# esp32_relay_attempt_1.net
KiCad netlist of a schematic drawn in EAGLE
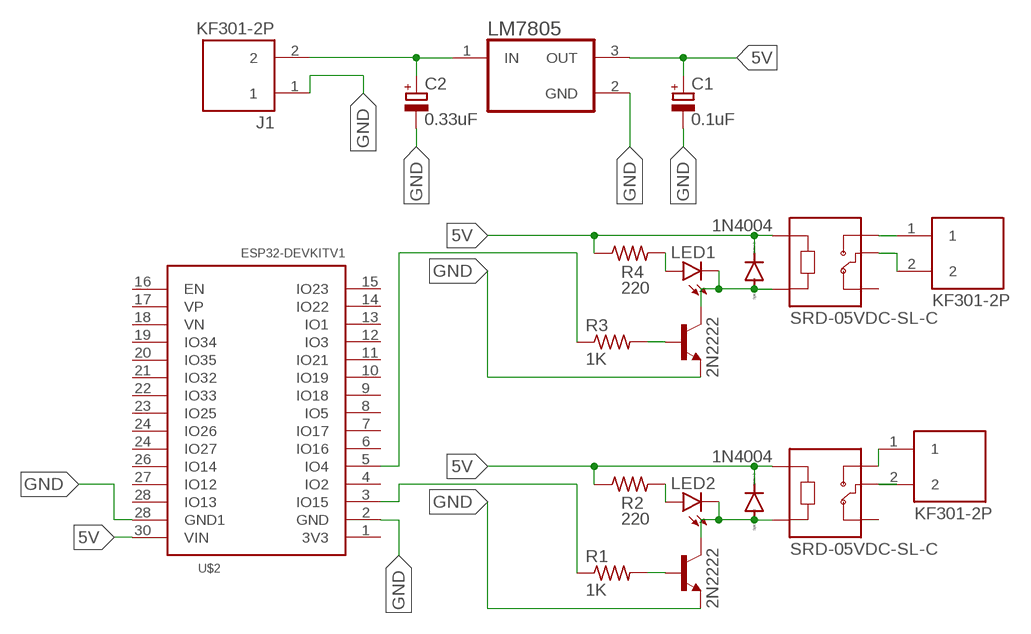
[diagram p0: schematic, sheet 1]

(export (version "E")
  (design (tool "Eeschema 10.0.6"))
  (components
    (comp (ref "C1")
      (value "0.1uF")
      (footprint "eagle-import:E2,5-6")
      (libsource (lib "eagle-import") (part "CPOL-EUE2.5-6"))
    )
    (comp (ref "C2")
      (value "0.33uF")
      (footprint "eagle-import:E2,5-6")
      (libsource (lib "eagle-import") (part "CPOL-EUE2.5-6"))
    )
    (comp (ref "D1")
      (value "1N4004")
      (footprint "eagle-import:DO41-10")
      (libsource (lib "eagle-import") (part "1N4004"))
    )
    (comp (ref "D2")
      (value "1N4004")
      (footprint "eagle-import:DO41-10")
      (libsource (lib "eagle-import") (part "1N4004"))
    )
    (comp (ref "J1")
      (value "KF301-2P")
      (footprint "eagle-import:HANDSON_KF301-2P")
      (fields (field (name "MF") "Handson Technology"))
      (libsource (lib "eagle-import") (part "KF301-2P"))
    )
    (comp (ref "J2")
      (value "KF301-2P")
      (footprint "eagle-import:HANDSON_KF301-2P")
      (fields (field (name "MF") "Handson Technology"))
      (libsource (lib "eagle-import") (part "KF301-2P"))
    )
    (comp (ref "J3")
      (value "KF301-2P")
      (footprint "eagle-import:HANDSON_KF301-2P")
      (fields (field (name "MF") "Handson Technology"))
      (libsource (lib "eagle-import") (part "KF301-2P"))
    )
    (comp (ref "K1")
      (value "SRD-05VDC-SL-C")
      (footprint "eagle-import:RELAY_SRD-05VDC-SL-C")
      (fields (field (name "MF") "Songle Relay"))
      (libsource (lib "eagle-import") (part "SRD-05VDC-SL-C"))
    )
    (comp (ref "K2")
      (value "SRD-05VDC-SL-C")
      (footprint "eagle-import:RELAY_SRD-05VDC-SL-C")
      (fields (field (name "MF") "Songle Relay"))
      (libsource (lib "eagle-import") (part "SRD-05VDC-SL-C"))
    )
    (comp (ref "LED1")
      (value "LED5MM")
      (footprint "eagle-import:LED5MM")
      (libsource (lib "eagle-import") (part "LED5MM"))
    )
    (comp (ref "LED2")
      (value "LED5MM")
      (footprint "eagle-import:LED5MM")
      (libsource (lib "eagle-import") (part "LED5MM"))
    )
    (comp (ref "LM7805")
      (value "LM7805CT/NOPB")
      (footprint "eagle-import:TO254P1054X470X2600-3")
      (fields (field (name "MF") "ON Semiconductor") (field (name "MP") "LM7805CT"))
      (libsource (lib "eagle-import") (part "LM7805CT/NOPB"))
    )
    (comp (ref "R1")
      (value "1K")
      (footprint "eagle-import:0204_7")
      (libsource (lib "eagle-import") (part "R-US_0204/7"))
    )
    (comp (ref "R2")
      (value "220")
      (footprint "eagle-import:0204_7")
      (libsource (lib "eagle-import") (part "R-US_0204/7"))
    )
    (comp (ref "R3")
      (value "1K")
      (footprint "eagle-import:0204_7")
      (libsource (lib "eagle-import") (part "R-US_0204/7"))
    )
    (comp (ref "R4")
      (value "220")
      (footprint "eagle-import:0204_7")
      (libsource (lib "eagle-import") (part "R-US_0204/7"))
    )
    (comp (ref "T1")
      (value "2N2222")
      (footprint "eagle-import:TO92-EBC-OVAL")
      (libsource (lib "eagle-import") (part "2N2222"))
    )
    (comp (ref "T2")
      (value "2N2222")
      (footprint "eagle-import:TO92-EBC-OVAL")
      (libsource (lib "eagle-import") (part "2N2222"))
    )
    (comp (ref "U$2")
      (value "ESP32DEVKITV1")
      (footprint "eagle-import:ESP32-DEVKITV1")
      (libsource (lib "eagle-import") (part "ESP32DEVKITV1"))
    )
  )
  (nets
    (net (code "1") (name "5V") (class "Default")
      (node (ref "C1") (pin "+") (pinfunction "+_+") (pintype "passive"))
      (node (ref "D1") (pin "C") (pinfunction "C_C") (pintype "passive"))
      (node (ref "D2") (pin "C") (pinfunction "C_C") (pintype "passive"))
      (node (ref "K1") (pin "A1") (pinfunction "A1_A1") (pintype "passive"))
      (node (ref "K2") (pin "A1") (pinfunction "A1_A1") (pintype "passive"))
      (node (ref "LM7805") (pin "3") (pinfunction "OUT_3") (pintype "output"))
      (node (ref "R2") (pin "1") (pinfunction "1_1") (pintype "passive"))
      (node (ref "R4") (pin "1") (pinfunction "1_1") (pintype "passive"))
      (node (ref "U$2") (pin "30") (pinfunction "VIN_30") (pintype "bidirectional"))
    )
    (net (code "2") (name "GND") (class "Default")
      (node (ref "C1") (pin "-") (pinfunction "-_-") (pintype "passive"))
      (node (ref "C2") (pin "-") (pinfunction "-_-") (pintype "passive"))
      (node (ref "J1") (pin "1") (pinfunction "1_1") (pintype "passive"))
      (node (ref "LM7805") (pin "2") (pinfunction "GND_2") (pintype "power_in"))
      (node (ref "T1") (pin "E") (pinfunction "E_E") (pintype "passive"))
      (node (ref "T2") (pin "E") (pinfunction "E_E") (pintype "passive"))
      (node (ref "U$2") (pin "2") (pinfunction "GND_2") (pintype "bidirectional"))
      (node (ref "U$2") (pin "28") (pinfunction "GND1_28") (pintype "bidirectional"))
    )
    (net (code "3") (name "Net-(J2-Pad1)") (class "Default")
      (node (ref "J2") (pin "1") (pinfunction "1_1") (pintype "passive"))
      (node (ref "K1") (pin "NO") (pinfunction "NO_NO") (pintype "passive"))
    )
    (net (code "4") (name "Net-(J2-Pad2)") (class "Default")
      (node (ref "J2") (pin "2") (pinfunction "2_2") (pintype "passive"))
      (node (ref "K1") (pin "COM") (pinfunction "COM_COM") (pintype "passive"))
    )
    (net (code "5") (name "Net-(J3-Pad1)") (class "Default")
      (node (ref "J3") (pin "1") (pinfunction "1_1") (pintype "passive"))
      (node (ref "K2") (pin "NO") (pinfunction "NO_NO") (pintype "passive"))
    )
    (net (code "6") (name "Net-(J3-Pad2)") (class "Default")
      (node (ref "J3") (pin "2") (pinfunction "2_2") (pintype "passive"))
      (node (ref "K2") (pin "COM") (pinfunction "COM_COM") (pintype "passive"))
    )
    (net (code "7") (name "Net-(LED1-C)") (class "Default")
      (node (ref "D1") (pin "A") (pinfunction "A_A") (pintype "passive"))
      (node (ref "K1") (pin "A2") (pinfunction "A2_A2") (pintype "passive"))
      (node (ref "LED1") (pin "K") (pinfunction "C_K") (pintype "passive"))
      (node (ref "T1") (pin "C") (pinfunction "C_C") (pintype "passive"))
    )
    (net (code "8") (name "Net-(LED1-PadA)") (class "Default")
      (node (ref "LED1") (pin "A") (pinfunction "A_A") (pintype "passive"))
      (node (ref "R4") (pin "2") (pinfunction "2_2") (pintype "passive"))
    )
    (net (code "9") (name "Net-(LED2-C)") (class "Default")
      (node (ref "D2") (pin "A") (pinfunction "A_A") (pintype "passive"))
      (node (ref "K2") (pin "A2") (pinfunction "A2_A2") (pintype "passive"))
      (node (ref "LED2") (pin "K") (pinfunction "C_K") (pintype "passive"))
      (node (ref "T2") (pin "C") (pinfunction "C_C") (pintype "passive"))
    )
    (net (code "10") (name "Net-(LED2-PadA)") (class "Default")
      (node (ref "LED2") (pin "A") (pinfunction "A_A") (pintype "passive"))
      (node (ref "R2") (pin "2") (pinfunction "2_2") (pintype "passive"))
    )
    (net (code "11") (name "Net-(LM7805-IN)") (class "Default")
      (node (ref "C2") (pin "+") (pinfunction "+_+") (pintype "passive"))
      (node (ref "J1") (pin "2") (pinfunction "2_2") (pintype "passive"))
      (node (ref "LM7805") (pin "1") (pinfunction "IN_1") (pintype "input"))
    )
    (net (code "12") (name "Net-(R1-Pad2)") (class "Default")
      (node (ref "R1") (pin "2") (pinfunction "2_2") (pintype "passive"))
      (node (ref "T2") (pin "B") (pinfunction "B_B") (pintype "passive"))
    )
    (net (code "13") (name "Net-(R3-Pad2)") (class "Default")
      (node (ref "R3") (pin "2") (pinfunction "2_2") (pintype "passive"))
      (node (ref "T1") (pin "B") (pinfunction "B_B") (pintype "passive"))
    )
    (net (code "14") (name "Net-(U$2-IO4)") (class "Default")
      (node (ref "R3") (pin "1") (pinfunction "1_1") (pintype "passive"))
      (node (ref "U$2") (pin "5") (pinfunction "IO4_5") (pintype "bidirectional"))
    )
    (net (code "15") (name "Net-(U$2-IO15)") (class "Default")
      (node (ref "R1") (pin "1") (pinfunction "1_1") (pintype "passive"))
      (node (ref "U$2") (pin "3") (pinfunction "IO15_3") (pintype "bidirectional"))
    )
    (net (code "16") (name "unconnected-(K1-PadNC)") (class "Default")
      (node (ref "K1") (pin "NC") (pinfunction "NC_NC") (pintype "passive"))
    )
    (net (code "17") (name "unconnected-(K2-PadNC)") (class "Default")
      (node (ref "K2") (pin "NC") (pinfunction "NC_NC") (pintype "passive"))
    )
    (net (code "18") (name "unconnected-(U$2-3V3-Pad1)") (class "Default")
      (node (ref "U$2") (pin "1") (pinfunction "3V3_1") (pintype "bidirectional"))
    )
    (net (code "19") (name "unconnected-(U$2-EN-Pad16)") (class "Default")
      (node (ref "U$2") (pin "16") (pinfunction "EN_16") (pintype "bidirectional"))
    )
    (net (code "20") (name "unconnected-(U$2-IO1-Pad13)") (class "Default")
      (node (ref "U$2") (pin "13") (pinfunction "IO1_13") (pintype "bidirectional"))
    )
    (net (code "21") (name "unconnected-(U$2-IO2-Pad4)") (class "Default")
      (node (ref "U$2") (pin "4") (pinfunction "IO2_4") (pintype "bidirectional"))
    )
    (net (code "22") (name "unconnected-(U$2-IO3-Pad12)") (class "Default")
      (node (ref "U$2") (pin "12") (pinfunction "IO3_12") (pintype "bidirectional"))
    )
    (net (code "23") (name "unconnected-(U$2-IO5-Pad8)") (class "Default")
      (node (ref "U$2") (pin "8") (pinfunction "IO5_8") (pintype "bidirectional"))
    )
    (net (code "24") (name "unconnected-(U$2-IO12-Pad27)") (class "Default")
      (node (ref "U$2") (pin "27") (pinfunction "IO12_27") (pintype "bidirectional"))
    )
    (net (code "25") (name "unconnected-(U$2-IO13-Pad28)") (class "Default")
      (node (ref "U$2") (pin "28") (pinfunction "IO13_28") (pintype "bidirectional"))
    )
    (net (code "26") (name "unconnected-(U$2-IO14-Pad26)") (class "Default")
      (node (ref "U$2") (pin "26") (pinfunction "IO14_26") (pintype "bidirectional"))
    )
    (net (code "27") (name "unconnected-(U$2-IO16-Pad6)") (class "Default")
      (node (ref "U$2") (pin "6") (pinfunction "IO16_6") (pintype "bidirectional"))
    )
    (net (code "28") (name "unconnected-(U$2-IO17-Pad7)") (class "Default")
      (node (ref "U$2") (pin "7") (pinfunction "IO17_7") (pintype "bidirectional"))
    )
    (net (code "29") (name "unconnected-(U$2-IO18-Pad9)") (class "Default")
      (node (ref "U$2") (pin "9") (pinfunction "IO18_9") (pintype "bidirectional"))
    )
    (net (code "30") (name "unconnected-(U$2-IO19-Pad10)") (class "Default")
      (node (ref "U$2") (pin "10") (pinfunction "IO19_10") (pintype "bidirectional"))
    )
    (net (code "31") (name "unconnected-(U$2-IO21-Pad11)") (class "Default")
      (node (ref "U$2") (pin "11") (pinfunction "IO21_11") (pintype "bidirectional"))
    )
    (net (code "32") (name "unconnected-(U$2-IO22-Pad14)") (class "Default")
      (node (ref "U$2") (pin "14") (pinfunction "IO22_14") (pintype "bidirectional"))
    )
    (net (code "33") (name "unconnected-(U$2-IO23-Pad15)") (class "Default")
      (node (ref "U$2") (pin "15") (pinfunction "IO23_15") (pintype "bidirectional"))
    )
    (net (code "34") (name "unconnected-(U$2-IO25-Pad23)") (class "Default")
      (node (ref "U$2") (pin "23") (pinfunction "IO25_23") (pintype "bidirectional"))
    )
    (net (code "35") (name "unconnected-(U$2-IO26-Pad24)") (class "Default")
      (node (ref "U$2") (pin "24") (pinfunction "IO26_24") (pintype "bidirectional"))
    )
    (net (code "36") (name "unconnected-(U$2-IO27-Pad24)") (class "Default")
      (node (ref "U$2") (pin "24") (pinfunction "IO27_24") (pintype "bidirectional"))
    )
    (net (code "37") (name "unconnected-(U$2-IO32-Pad21)") (class "Default")
      (node (ref "U$2") (pin "21") (pinfunction "IO32_21") (pintype "bidirectional"))
    )
    (net (code "38") (name "unconnected-(U$2-IO33-Pad22)") (class "Default")
      (node (ref "U$2") (pin "22") (pinfunction "IO33_22") (pintype "bidirectional"))
    )
    (net (code "39") (name "unconnected-(U$2-IO34-Pad19)") (class "Default")
      (node (ref "U$2") (pin "19") (pinfunction "IO34_19") (pintype "bidirectional"))
    )
    (net (code "40") (name "unconnected-(U$2-IO35-Pad20)") (class "Default")
      (node (ref "U$2") (pin "20") (pinfunction "IO35_20") (pintype "bidirectional"))
    )
    (net (code "41") (name "unconnected-(U$2-VN-Pad18)") (class "Default")
      (node (ref "U$2") (pin "18") (pinfunction "VN_18") (pintype "bidirectional"))
    )
    (net (code "42") (name "unconnected-(U$2-VP-Pad17)") (class "Default")
      (node (ref "U$2") (pin "17") (pinfunction "VP_17") (pintype "bidirectional"))
    )
  )
)
